# untitled.net
KiCad netlist of a schematic drawn in EAGLE
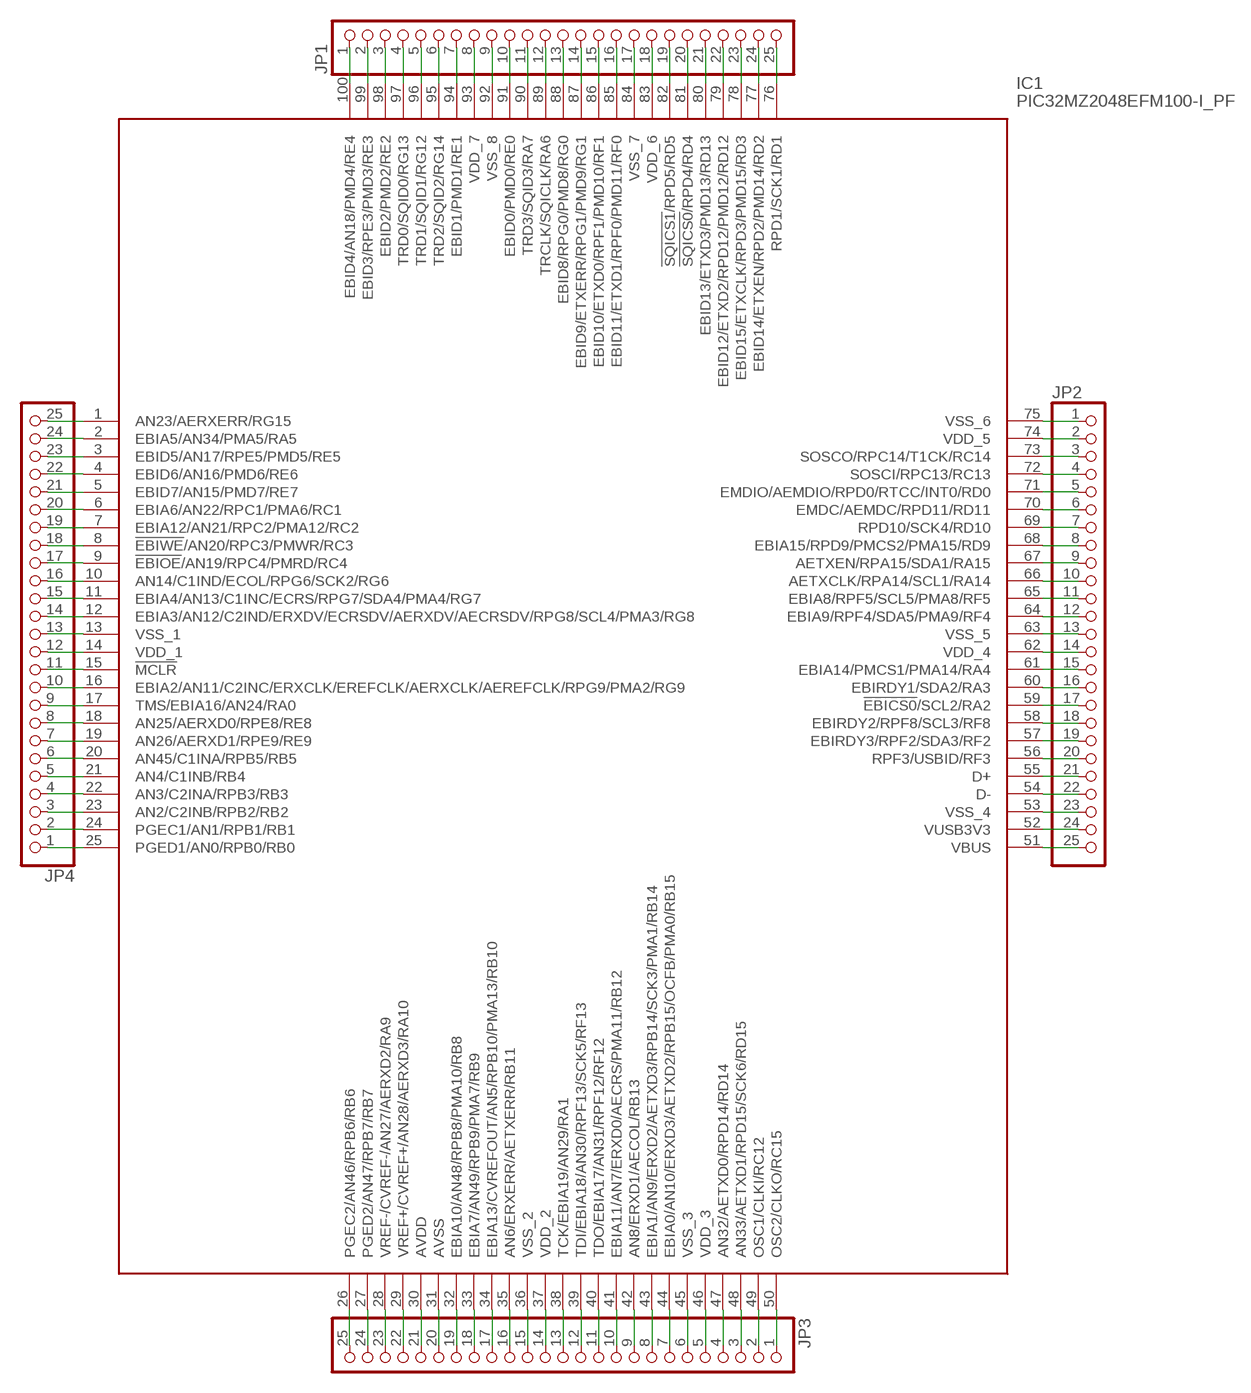
[diagram p0: schematic, sheet 1]

(export (version "E")
  (design (tool "Eeschema 10.0.6"))
  (components
    (comp (ref "IC1")
      (value "PIC32MZ2048EFM100-I_PF")
      (footprint "eagle-import:QFP50P1600X1600X120-100N")
      (fields
        (field (name "MANUFACTURER_PART_NUMBER") "PIC32MZ2048EFM100-I/PF")
        (field (name "MOUSER_PART_NUMBER") "579-MZ2048EFM100IPF")
        (field (name "RS_PART_NUMBER") "1654261")
      )
      (libsource (lib "eagle-import") (part "PIC32MZ2048EFM100-I_PF"))
    )
    (comp (ref "JP1")
      (value "PINHD-1X25")
      (footprint "eagle-import:1X25")
      (libsource (lib "eagle-import") (part "PINHD-1X25"))
    )
    (comp (ref "JP2")
      (value "PINHD-1X25")
      (footprint "eagle-import:1X25")
      (libsource (lib "eagle-import") (part "PINHD-1X25"))
    )
    (comp (ref "JP3")
      (value "PINHD-1X25")
      (footprint "eagle-import:1X25")
      (libsource (lib "eagle-import") (part "PINHD-1X25"))
    )
    (comp (ref "JP4")
      (value "PINHD-1X25")
      (footprint "eagle-import:1X25")
      (libsource (lib "eagle-import") (part "PINHD-1X25"))
    )
  )
  (nets
    (net (code "1") (name "Net-(IC1-AETXCLK{slash}RPA14{slash}SCL1{slash}RA14)") (class "Default")
      (node (ref "IC1") (pin "66") (pinfunction "AETXCLK/RPA14/SCL1/RA14_66") (pintype "bidirectional"))
      (node (ref "JP2") (pin "10") (pinfunction "10_10") (pintype "passive"))
    )
    (net (code "2") (name "Net-(IC1-AETXEN{slash}RPA15{slash}SDA1{slash}RA15)") (class "Default")
      (node (ref "IC1") (pin "67") (pinfunction "AETXEN/RPA15/SDA1/RA15_67") (pintype "bidirectional"))
      (node (ref "JP2") (pin "9") (pinfunction "9_9") (pintype "passive"))
    )
    (net (code "3") (name "Net-(IC1-AN2{slash}C2INB{slash}RPB2{slash}RB2)") (class "Default")
      (node (ref "IC1") (pin "23") (pinfunction "AN2/C2INB/RPB2/RB2_23") (pintype "bidirectional"))
      (node (ref "JP4") (pin "3") (pinfunction "3_3") (pintype "passive"))
    )
    (net (code "4") (name "Net-(IC1-AN3{slash}C2INA{slash}RPB3{slash}RB3)") (class "Default")
      (node (ref "IC1") (pin "22") (pinfunction "AN3/C2INA/RPB3/RB3_22") (pintype "bidirectional"))
      (node (ref "JP4") (pin "4") (pinfunction "4_4") (pintype "passive"))
    )
    (net (code "5") (name "Net-(IC1-AN4{slash}C1INB{slash}RB4)") (class "Default")
      (node (ref "IC1") (pin "21") (pinfunction "AN4/C1INB/RB4_21") (pintype "bidirectional"))
      (node (ref "JP4") (pin "5") (pinfunction "5_5") (pintype "passive"))
    )
    (net (code "6") (name "Net-(IC1-AN6{slash}ERXERR{slash}AETXERR{slash}RB11)") (class "Default")
      (node (ref "IC1") (pin "35") (pinfunction "AN6/ERXERR/AETXERR/RB11_35") (pintype "bidirectional"))
      (node (ref "JP3") (pin "16") (pinfunction "16_16") (pintype "passive"))
    )
    (net (code "7") (name "Net-(IC1-AN8{slash}ERXD1{slash}AECOL{slash}RB13)") (class "Default")
      (node (ref "IC1") (pin "42") (pinfunction "AN8/ERXD1/AECOL/RB13_42") (pintype "bidirectional"))
      (node (ref "JP3") (pin "9") (pinfunction "9_9") (pintype "passive"))
    )
    (net (code "8") (name "Net-(IC1-AN14{slash}C1IND{slash}ECOL{slash}RPG6{slash}SCK2{slash}RG6)") (class "Default")
      (node (ref "IC1") (pin "10") (pinfunction "AN14/C1IND/ECOL/RPG6/SCK2/RG6_10") (pintype "bidirectional"))
      (node (ref "JP4") (pin "16") (pinfunction "16_16") (pintype "passive"))
    )
    (net (code "9") (name "Net-(IC1-AN23{slash}AERXERR{slash}RG15)") (class "Default")
      (node (ref "IC1") (pin "1") (pinfunction "AN23/AERXERR/RG15_1") (pintype "bidirectional"))
      (node (ref "JP4") (pin "25") (pinfunction "25_25") (pintype "passive"))
    )
    (net (code "10") (name "Net-(IC1-AN25{slash}AERXD0{slash}RPE8{slash}RE8)") (class "Default")
      (node (ref "IC1") (pin "18") (pinfunction "AN25/AERXD0/RPE8/RE8_18") (pintype "bidirectional"))
      (node (ref "JP4") (pin "8") (pinfunction "8_8") (pintype "passive"))
    )
    (net (code "11") (name "Net-(IC1-AN26{slash}AERXD1{slash}RPE9{slash}RE9)") (class "Default")
      (node (ref "IC1") (pin "19") (pinfunction "AN26/AERXD1/RPE9/RE9_19") (pintype "bidirectional"))
      (node (ref "JP4") (pin "7") (pinfunction "7_7") (pintype "passive"))
    )
    (net (code "12") (name "Net-(IC1-AN32{slash}AETXD0{slash}RPD14{slash}RD14)") (class "Default")
      (node (ref "IC1") (pin "47") (pinfunction "AN32/AETXD0/RPD14/RD14_47") (pintype "bidirectional"))
      (node (ref "JP3") (pin "4") (pinfunction "4_4") (pintype "passive"))
    )
    (net (code "13") (name "Net-(IC1-AN33{slash}AETXD1{slash}RPD15{slash}SCK6{slash}RD15)") (class "Default")
      (node (ref "IC1") (pin "48") (pinfunction "AN33/AETXD1/RPD15/SCK6/RD15_48") (pintype "bidirectional"))
      (node (ref "JP3") (pin "3") (pinfunction "3_3") (pintype "passive"))
    )
    (net (code "14") (name "Net-(IC1-AN45{slash}C1INA{slash}RPB5{slash}RB5)") (class "Default")
      (node (ref "IC1") (pin "20") (pinfunction "AN45/C1INA/RPB5/RB5_20") (pintype "bidirectional"))
      (node (ref "JP4") (pin "6") (pinfunction "6_6") (pintype "passive"))
    )
    (net (code "15") (name "Net-(IC1-AVDD)") (class "Default")
      (node (ref "IC1") (pin "30") (pinfunction "AVDD_30") (pintype "power_in"))
      (node (ref "JP3") (pin "21") (pinfunction "21_21") (pintype "passive"))
    )
    (net (code "16") (name "Net-(IC1-AVSS)") (class "Default")
      (node (ref "IC1") (pin "31") (pinfunction "AVSS_31") (pintype "power_in"))
      (node (ref "JP3") (pin "20") (pinfunction "20_20") (pintype "passive"))
    )
    (net (code "17") (name "Net-(IC1-D+)") (class "Default")
      (node (ref "IC1") (pin "55") (pinfunction "D+_55") (pintype "bidirectional"))
      (node (ref "JP2") (pin "21") (pinfunction "21_21") (pintype "passive"))
    )
    (net (code "18") (name "Net-(IC1-D-)") (class "Default")
      (node (ref "IC1") (pin "54") (pinfunction "D-_54") (pintype "bidirectional"))
      (node (ref "JP2") (pin "22") (pinfunction "22_22") (pintype "passive"))
    )
    (net (code "19") (name "Net-(IC1-EBIA0{slash}AN10{slash}ERXD3{slash}AETXD2{slash}RPB15{slash}OCFB{slash}PMA0{slash}RB15)") (class "Default")
      (node (ref "IC1") (pin "44") (pinfunction "EBIA0/AN10/ERXD3/AETXD2/RPB15/OCFB/PMA0/RB15_44") (pintype "bidirectional"))
      (node (ref "JP3") (pin "7") (pinfunction "7_7") (pintype "passive"))
    )
    (net (code "20") (name "Net-(IC1-EBIA1{slash}AN9{slash}ERXD2{slash}AETXD3{slash}RPB14{slash}SCK3{slash}PMA1{slash}RB14)") (class "Default")
      (node (ref "IC1") (pin "43") (pinfunction "EBIA1/AN9/ERXD2/AETXD3/RPB14/SCK3/PMA1/RB14_43") (pintype "bidirectional"))
      (node (ref "JP3") (pin "8") (pinfunction "8_8") (pintype "passive"))
    )
    (net (code "21") (name "Net-(IC1-EBIA2{slash}AN11{slash}C2INC{slash}ERXCLK{slash}EREFCLK{slash}AERXCLK{slash}AEREFCLK{slash}RPG9{slash}PMA2{slash}RG9)") (class "Default")
      (node (ref "IC1") (pin "16") (pinfunction "EBIA2/AN11/C2INC/ERXCLK/EREFCLK/AERXCLK/AEREFCLK/RPG9/PMA2/RG9_16") (pintype "bidirectional"))
      (node (ref "JP4") (pin "10") (pinfunction "10_10") (pintype "passive"))
    )
    (net (code "22") (name "Net-(IC1-EBIA3{slash}AN12{slash}C2IND{slash}ERXDV{slash}ECRSDV{slash}AERXDV{slash}AECRSDV{slash}RPG8{slash}SCL4{slash}PMA3{slash}RG8)") (class "Default")
      (node (ref "IC1") (pin "12") (pinfunction "EBIA3/AN12/C2IND/ERXDV/ECRSDV/AERXDV/AECRSDV/RPG8/SCL4/PMA3/RG8_12") (pintype "bidirectional"))
      (node (ref "JP4") (pin "14") (pinfunction "14_14") (pintype "passive"))
    )
    (net (code "23") (name "Net-(IC1-EBIA4{slash}AN13{slash}C1INC{slash}ECRS{slash}RPG7{slash}SDA4{slash}PMA4{slash}RG7)") (class "Default")
      (node (ref "IC1") (pin "11") (pinfunction "EBIA4/AN13/C1INC/ECRS/RPG7/SDA4/PMA4/RG7_11") (pintype "bidirectional"))
      (node (ref "JP4") (pin "15") (pinfunction "15_15") (pintype "passive"))
    )
    (net (code "24") (name "Net-(IC1-EBIA5{slash}AN34{slash}PMA5{slash}RA5)") (class "Default")
      (node (ref "IC1") (pin "2") (pinfunction "EBIA5/AN34/PMA5/RA5_2") (pintype "bidirectional"))
      (node (ref "JP4") (pin "24") (pinfunction "24_24") (pintype "passive"))
    )
    (net (code "25") (name "Net-(IC1-EBIA6{slash}AN22{slash}RPC1{slash}PMA6{slash}RC1)") (class "Default")
      (node (ref "IC1") (pin "6") (pinfunction "EBIA6/AN22/RPC1/PMA6/RC1_6") (pintype "bidirectional"))
      (node (ref "JP4") (pin "20") (pinfunction "20_20") (pintype "passive"))
    )
    (net (code "26") (name "Net-(IC1-EBIA7{slash}AN49{slash}RPB9{slash}PMA7{slash}RB9)") (class "Default")
      (node (ref "IC1") (pin "33") (pinfunction "EBIA7/AN49/RPB9/PMA7/RB9_33") (pintype "bidirectional"))
      (node (ref "JP3") (pin "18") (pinfunction "18_18") (pintype "passive"))
    )
    (net (code "27") (name "Net-(IC1-EBIA8{slash}RPF5{slash}SCL5{slash}PMA8{slash}RF5)") (class "Default")
      (node (ref "IC1") (pin "65") (pinfunction "EBIA8/RPF5/SCL5/PMA8/RF5_65") (pintype "bidirectional"))
      (node (ref "JP2") (pin "11") (pinfunction "11_11") (pintype "passive"))
    )
    (net (code "28") (name "Net-(IC1-EBIA9{slash}RPF4{slash}SDA5{slash}PMA9{slash}RF4)") (class "Default")
      (node (ref "IC1") (pin "64") (pinfunction "EBIA9/RPF4/SDA5/PMA9/RF4_64") (pintype "bidirectional"))
      (node (ref "JP2") (pin "12") (pinfunction "12_12") (pintype "passive"))
    )
    (net (code "29") (name "Net-(IC1-EBIA10{slash}AN48{slash}RPB8{slash}PMA10{slash}RB8)") (class "Default")
      (node (ref "IC1") (pin "32") (pinfunction "EBIA10/AN48/RPB8/PMA10/RB8_32") (pintype "bidirectional"))
      (node (ref "JP3") (pin "19") (pinfunction "19_19") (pintype "passive"))
    )
    (net (code "30") (name "Net-(IC1-EBIA11{slash}AN7{slash}ERXD0{slash}AECRS{slash}PMA11{slash}RB12)") (class "Default")
      (node (ref "IC1") (pin "41") (pinfunction "EBIA11/AN7/ERXD0/AECRS/PMA11/RB12_41") (pintype "bidirectional"))
      (node (ref "JP3") (pin "10") (pinfunction "10_10") (pintype "passive"))
    )
    (net (code "31") (name "Net-(IC1-EBIA12{slash}AN21{slash}RPC2{slash}PMA12{slash}RC2)") (class "Default")
      (node (ref "IC1") (pin "7") (pinfunction "EBIA12/AN21/RPC2/PMA12/RC2_7") (pintype "bidirectional"))
      (node (ref "JP4") (pin "19") (pinfunction "19_19") (pintype "passive"))
    )
    (net (code "32") (name "Net-(IC1-EBIA13{slash}CVREFOUT{slash}AN5{slash}RPB10{slash}PMA13{slash}RB10)") (class "Default")
      (node (ref "IC1") (pin "34") (pinfunction "EBIA13/CVREFOUT/AN5/RPB10/PMA13/RB10_34") (pintype "bidirectional"))
      (node (ref "JP3") (pin "17") (pinfunction "17_17") (pintype "passive"))
    )
    (net (code "33") (name "Net-(IC1-EBIA14{slash}PMCS1{slash}PMA14{slash}RA4)") (class "Default")
      (node (ref "IC1") (pin "61") (pinfunction "EBIA14/PMCS1/PMA14/RA4_61") (pintype "bidirectional"))
      (node (ref "JP2") (pin "15") (pinfunction "15_15") (pintype "passive"))
    )
    (net (code "34") (name "Net-(IC1-EBIA15{slash}RPD9{slash}PMCS2{slash}PMA15{slash}RD9)") (class "Default")
      (node (ref "IC1") (pin "68") (pinfunction "EBIA15/RPD9/PMCS2/PMA15/RD9_68") (pintype "bidirectional"))
      (node (ref "JP2") (pin "8") (pinfunction "8_8") (pintype "passive"))
    )
    (net (code "35") (name "Net-(IC1-EBID0{slash}PMD0{slash}RE0)") (class "Default")
      (node (ref "IC1") (pin "91") (pinfunction "EBID0/PMD0/RE0_91") (pintype "bidirectional"))
      (node (ref "JP1") (pin "10") (pinfunction "10_10") (pintype "passive"))
    )
    (net (code "36") (name "Net-(IC1-EBID1{slash}PMD1{slash}RE1)") (class "Default")
      (node (ref "IC1") (pin "94") (pinfunction "EBID1/PMD1/RE1_94") (pintype "bidirectional"))
      (node (ref "JP1") (pin "7") (pinfunction "7_7") (pintype "passive"))
    )
    (net (code "37") (name "Net-(IC1-EBID2{slash}PMD2{slash}RE2)") (class "Default")
      (node (ref "IC1") (pin "98") (pinfunction "EBID2/PMD2/RE2_98") (pintype "bidirectional"))
      (node (ref "JP1") (pin "3") (pinfunction "3_3") (pintype "passive"))
    )
    (net (code "38") (name "Net-(IC1-EBID3{slash}RPE3{slash}PMD3{slash}RE3)") (class "Default")
      (node (ref "IC1") (pin "99") (pinfunction "EBID3/RPE3/PMD3/RE3_99") (pintype "bidirectional"))
      (node (ref "JP1") (pin "2") (pinfunction "2_2") (pintype "passive"))
    )
    (net (code "39") (name "Net-(IC1-EBID4{slash}AN18{slash}PMD4{slash}RE4)") (class "Default")
      (node (ref "IC1") (pin "100") (pinfunction "EBID4/AN18/PMD4/RE4_100") (pintype "bidirectional"))
      (node (ref "JP1") (pin "1") (pinfunction "1_1") (pintype "passive"))
    )
    (net (code "40") (name "Net-(IC1-EBID5{slash}AN17{slash}RPE5{slash}PMD5{slash}RE5)") (class "Default")
      (node (ref "IC1") (pin "3") (pinfunction "EBID5/AN17/RPE5/PMD5/RE5_3") (pintype "bidirectional"))
      (node (ref "JP4") (pin "23") (pinfunction "23_23") (pintype "passive"))
    )
    (net (code "41") (name "Net-(IC1-EBID6{slash}AN16{slash}PMD6{slash}RE6)") (class "Default")
      (node (ref "IC1") (pin "4") (pinfunction "EBID6/AN16/PMD6/RE6_4") (pintype "bidirectional"))
      (node (ref "JP4") (pin "22") (pinfunction "22_22") (pintype "passive"))
    )
    (net (code "42") (name "Net-(IC1-EBID7{slash}AN15{slash}PMD7{slash}RE7)") (class "Default")
      (node (ref "IC1") (pin "5") (pinfunction "EBID7/AN15/PMD7/RE7_5") (pintype "bidirectional"))
      (node (ref "JP4") (pin "21") (pinfunction "21_21") (pintype "passive"))
    )
    (net (code "43") (name "Net-(IC1-EBID8{slash}RPG0{slash}PMD8{slash}RG0)") (class "Default")
      (node (ref "IC1") (pin "88") (pinfunction "EBID8/RPG0/PMD8/RG0_88") (pintype "bidirectional"))
      (node (ref "JP1") (pin "13") (pinfunction "13_13") (pintype "passive"))
    )
    (net (code "44") (name "Net-(IC1-EBID9{slash}ETXERR{slash}RPG1{slash}PMD9{slash}RG1)") (class "Default")
      (node (ref "IC1") (pin "87") (pinfunction "EBID9/ETXERR/RPG1/PMD9/RG1_87") (pintype "bidirectional"))
      (node (ref "JP1") (pin "14") (pinfunction "14_14") (pintype "passive"))
    )
    (net (code "45") (name "Net-(IC1-EBID10{slash}ETXD0{slash}RPF1{slash}PMD10{slash}RF1)") (class "Default")
      (node (ref "IC1") (pin "86") (pinfunction "EBID10/ETXD0/RPF1/PMD10/RF1_86") (pintype "bidirectional"))
      (node (ref "JP1") (pin "15") (pinfunction "15_15") (pintype "passive"))
    )
    (net (code "46") (name "Net-(IC1-EBID11{slash}ETXD1{slash}RPF0{slash}PMD11{slash}RF0)") (class "Default")
      (node (ref "IC1") (pin "85") (pinfunction "EBID11/ETXD1/RPF0/PMD11/RF0_85") (pintype "bidirectional"))
      (node (ref "JP1") (pin "16") (pinfunction "16_16") (pintype "passive"))
    )
    (net (code "47") (name "Net-(IC1-EBID12{slash}ETXD2{slash}RPD12{slash}PMD12{slash}RD12)") (class "Default")
      (node (ref "IC1") (pin "79") (pinfunction "EBID12/ETXD2/RPD12/PMD12/RD12_79") (pintype "bidirectional"))
      (node (ref "JP1") (pin "22") (pinfunction "22_22") (pintype "passive"))
    )
    (net (code "48") (name "Net-(IC1-EBID13{slash}ETXD3{slash}PMD13{slash}RD13)") (class "Default")
      (node (ref "IC1") (pin "80") (pinfunction "EBID13/ETXD3/PMD13/RD13_80") (pintype "bidirectional"))
      (node (ref "JP1") (pin "21") (pinfunction "21_21") (pintype "passive"))
    )
    (net (code "49") (name "Net-(IC1-EBID14{slash}ETXEN{slash}RPD2{slash}PMD14{slash}RD2)") (class "Default")
      (node (ref "IC1") (pin "77") (pinfunction "EBID14/ETXEN/RPD2/PMD14/RD2_77") (pintype "bidirectional"))
      (node (ref "JP1") (pin "24") (pinfunction "24_24") (pintype "passive"))
    )
    (net (code "50") (name "Net-(IC1-EBID15{slash}ETXCLK{slash}RPD3{slash}PMD15{slash}RD3)") (class "Default")
      (node (ref "IC1") (pin "78") (pinfunction "EBID15/ETXCLK/RPD3/PMD15/RD3_78") (pintype "bidirectional"))
      (node (ref "JP1") (pin "23") (pinfunction "23_23") (pintype "passive"))
    )
    (net (code "51") (name "Net-(IC1-EBIRDY1{slash}SDA2{slash}RA3)") (class "Default")
      (node (ref "IC1") (pin "60") (pinfunction "EBIRDY1/SDA2/RA3_60") (pintype "bidirectional"))
      (node (ref "JP2") (pin "16") (pinfunction "16_16") (pintype "passive"))
    )
    (net (code "52") (name "Net-(IC1-EBIRDY2{slash}RPF8{slash}SCL3{slash}RF8)") (class "Default")
      (node (ref "IC1") (pin "58") (pinfunction "EBIRDY2/RPF8/SCL3/RF8_58") (pintype "bidirectional"))
      (node (ref "JP2") (pin "18") (pinfunction "18_18") (pintype "passive"))
    )
    (net (code "53") (name "Net-(IC1-EBIRDY3{slash}RPF2{slash}SDA3{slash}RF2)") (class "Default")
      (node (ref "IC1") (pin "57") (pinfunction "EBIRDY3/RPF2/SDA3/RF2_57") (pintype "bidirectional"))
      (node (ref "JP2") (pin "19") (pinfunction "19_19") (pintype "passive"))
    )
    (net (code "54") (name "Net-(IC1-EMDC{slash}AEMDC{slash}RPD11{slash}RD11)") (class "Default")
      (node (ref "IC1") (pin "70") (pinfunction "EMDC/AEMDC/RPD11/RD11_70") (pintype "bidirectional"))
      (node (ref "JP2") (pin "6") (pinfunction "6_6") (pintype "passive"))
    )
    (net (code "55") (name "Net-(IC1-EMDIO{slash}AEMDIO{slash}RPD0{slash}RTCC{slash}INT0{slash}RD0)") (class "Default")
      (node (ref "IC1") (pin "71") (pinfunction "EMDIO/AEMDIO/RPD0/RTCC/INT0/RD0_71") (pintype "bidirectional"))
      (node (ref "JP2") (pin "5") (pinfunction "5_5") (pintype "passive"))
    )
    (net (code "56") (name "Net-(IC1-OSC1{slash}CLKI{slash}RC12)") (class "Default")
      (node (ref "IC1") (pin "49") (pinfunction "OSC1/CLKI/RC12_49") (pintype "bidirectional"))
      (node (ref "JP3") (pin "2") (pinfunction "2_2") (pintype "passive"))
    )
    (net (code "57") (name "Net-(IC1-OSC2{slash}CLKO{slash}RC15)") (class "Default")
      (node (ref "IC1") (pin "50") (pinfunction "OSC2/CLKO/RC15_50") (pintype "bidirectional"))
      (node (ref "JP3") (pin "1") (pinfunction "1_1") (pintype "passive"))
    )
    (net (code "58") (name "Net-(IC1-PGEC1{slash}AN1{slash}RPB1{slash}RB1)") (class "Default")
      (node (ref "IC1") (pin "24") (pinfunction "PGEC1/AN1/RPB1/RB1_24") (pintype "bidirectional"))
      (node (ref "JP4") (pin "2") (pinfunction "2_2") (pintype "passive"))
    )
    (net (code "59") (name "Net-(IC1-PGEC2{slash}AN46{slash}RPB6{slash}RB6)") (class "Default")
      (node (ref "IC1") (pin "26") (pinfunction "PGEC2/AN46/RPB6/RB6_26") (pintype "bidirectional"))
      (node (ref "JP3") (pin "25") (pinfunction "25_25") (pintype "passive"))
    )
    (net (code "60") (name "Net-(IC1-PGED1{slash}AN0{slash}RPB0{slash}RB0)") (class "Default")
      (node (ref "IC1") (pin "25") (pinfunction "PGED1/AN0/RPB0/RB0_25") (pintype "bidirectional"))
      (node (ref "JP4") (pin "1") (pinfunction "1_1") (pintype "passive"))
    )
    (net (code "61") (name "Net-(IC1-PGED2{slash}AN47{slash}RPB7{slash}RB7)") (class "Default")
      (node (ref "IC1") (pin "27") (pinfunction "PGED2/AN47/RPB7/RB7_27") (pintype "bidirectional"))
      (node (ref "JP3") (pin "24") (pinfunction "24_24") (pintype "passive"))
    )
    (net (code "62") (name "Net-(IC1-RPD1{slash}SCK1{slash}RD1)") (class "Default")
      (node (ref "IC1") (pin "76") (pinfunction "RPD1/SCK1/RD1_76") (pintype "bidirectional"))
      (node (ref "JP1") (pin "25") (pinfunction "25_25") (pintype "passive"))
    )
    (net (code "63") (name "Net-(IC1-RPD10{slash}SCK4{slash}RD10)") (class "Default")
      (node (ref "IC1") (pin "69") (pinfunction "RPD10/SCK4/RD10_69") (pintype "bidirectional"))
      (node (ref "JP2") (pin "7") (pinfunction "7_7") (pintype "passive"))
    )
    (net (code "64") (name "Net-(IC1-RPF3{slash}USBID{slash}RF3)") (class "Default")
      (node (ref "IC1") (pin "56") (pinfunction "RPF3/USBID/RF3_56") (pintype "bidirectional"))
      (node (ref "JP2") (pin "20") (pinfunction "20_20") (pintype "passive"))
    )
    (net (code "65") (name "Net-(IC1-SOSCI{slash}RPC13{slash}RC13)") (class "Default")
      (node (ref "IC1") (pin "72") (pinfunction "SOSCI/RPC13/RC13_72") (pintype "bidirectional"))
      (node (ref "JP2") (pin "4") (pinfunction "4_4") (pintype "passive"))
    )
    (net (code "66") (name "Net-(IC1-SOSCO{slash}RPC14{slash}T1CK{slash}RC14)") (class "Default")
      (node (ref "IC1") (pin "73") (pinfunction "SOSCO/RPC14/T1CK/RC14_73") (pintype "bidirectional"))
      (node (ref "JP2") (pin "3") (pinfunction "3_3") (pintype "passive"))
    )
    (net (code "67") (name "Net-(IC1-TCK{slash}EBIA19{slash}AN29{slash}RA1)") (class "Default")
      (node (ref "IC1") (pin "38") (pinfunction "TCK/EBIA19/AN29/RA1_38") (pintype "bidirectional"))
      (node (ref "JP3") (pin "13") (pinfunction "13_13") (pintype "passive"))
    )
    (net (code "68") (name "Net-(IC1-TDI{slash}EBIA18{slash}AN30{slash}RPF13{slash}SCK5{slash}RF13)") (class "Default")
      (node (ref "IC1") (pin "39") (pinfunction "TDI/EBIA18/AN30/RPF13/SCK5/RF13_39") (pintype "bidirectional"))
      (node (ref "JP3") (pin "12") (pinfunction "12_12") (pintype "passive"))
    )
    (net (code "69") (name "Net-(IC1-TDO{slash}EBIA17{slash}AN31{slash}RPF12{slash}RF12)") (class "Default")
      (node (ref "IC1") (pin "40") (pinfunction "TDO/EBIA17/AN31/RPF12/RF12_40") (pintype "bidirectional"))
      (node (ref "JP3") (pin "11") (pinfunction "11_11") (pintype "passive"))
    )
    (net (code "70") (name "Net-(IC1-TMS{slash}EBIA16{slash}AN24{slash}RA0)") (class "Default")
      (node (ref "IC1") (pin "17") (pinfunction "TMS/EBIA16/AN24/RA0_17") (pintype "bidirectional"))
      (node (ref "JP4") (pin "9") (pinfunction "9_9") (pintype "passive"))
    )
    (net (code "71") (name "Net-(IC1-TRCLK{slash}SQICLK{slash}RA6)") (class "Default")
      (node (ref "IC1") (pin "89") (pinfunction "TRCLK/SQICLK/RA6_89") (pintype "bidirectional"))
      (node (ref "JP1") (pin "12") (pinfunction "12_12") (pintype "passive"))
    )
    (net (code "72") (name "Net-(IC1-TRD0{slash}SQID0{slash}RG13)") (class "Default")
      (node (ref "IC1") (pin "97") (pinfunction "TRD0/SQID0/RG13_97") (pintype "bidirectional"))
      (node (ref "JP1") (pin "4") (pinfunction "4_4") (pintype "passive"))
    )
    (net (code "73") (name "Net-(IC1-TRD1{slash}SQID1{slash}RG12)") (class "Default")
      (node (ref "IC1") (pin "96") (pinfunction "TRD1/SQID1/RG12_96") (pintype "bidirectional"))
      (node (ref "JP1") (pin "5") (pinfunction "5_5") (pintype "passive"))
    )
    (net (code "74") (name "Net-(IC1-TRD2{slash}SQID2{slash}RG14)") (class "Default")
      (node (ref "IC1") (pin "95") (pinfunction "TRD2/SQID2/RG14_95") (pintype "bidirectional"))
      (node (ref "JP1") (pin "6") (pinfunction "6_6") (pintype "passive"))
    )
    (net (code "75") (name "Net-(IC1-TRD3{slash}SQID3{slash}RA7)") (class "Default")
      (node (ref "IC1") (pin "90") (pinfunction "TRD3/SQID3/RA7_90") (pintype "bidirectional"))
      (node (ref "JP1") (pin "11") (pinfunction "11_11") (pintype "passive"))
    )
    (net (code "76") (name "Net-(IC1-VBUS)") (class "Default")
      (node (ref "IC1") (pin "51") (pinfunction "VBUS_51") (pintype "power_in"))
      (node (ref "JP2") (pin "25") (pinfunction "25_25") (pintype "passive"))
    )
    (net (code "77") (name "Net-(IC1-VDD_1)") (class "Default")
      (node (ref "IC1") (pin "14") (pinfunction "VDD_1_14") (pintype "power_in"))
      (node (ref "JP4") (pin "12") (pinfunction "12_12") (pintype "passive"))
    )
    (net (code "78") (name "Net-(IC1-VDD_2)") (class "Default")
      (node (ref "IC1") (pin "37") (pinfunction "VDD_2_37") (pintype "power_in"))
      (node (ref "JP3") (pin "14") (pinfunction "14_14") (pintype "passive"))
    )
    (net (code "79") (name "Net-(IC1-VDD_3)") (class "Default")
      (node (ref "IC1") (pin "46") (pinfunction "VDD_3_46") (pintype "power_in"))
      (node (ref "JP3") (pin "5") (pinfunction "5_5") (pintype "passive"))
    )
    (net (code "80") (name "Net-(IC1-VDD_4)") (class "Default")
      (node (ref "IC1") (pin "62") (pinfunction "VDD_4_62") (pintype "power_in"))
      (node (ref "JP2") (pin "14") (pinfunction "14_14") (pintype "passive"))
    )
    (net (code "81") (name "Net-(IC1-VDD_5)") (class "Default")
      (node (ref "IC1") (pin "74") (pinfunction "VDD_5_74") (pintype "power_in"))
      (node (ref "JP2") (pin "2") (pinfunction "2_2") (pintype "passive"))
    )
    (net (code "82") (name "Net-(IC1-VDD_6)") (class "Default")
      (node (ref "IC1") (pin "83") (pinfunction "VDD_6_83") (pintype "power_in"))
      (node (ref "JP1") (pin "18") (pinfunction "18_18") (pintype "passive"))
    )
    (net (code "83") (name "Net-(IC1-VDD_7)") (class "Default")
      (node (ref "IC1") (pin "93") (pinfunction "VDD_7_93") (pintype "power_in"))
      (node (ref "JP1") (pin "8") (pinfunction "8_8") (pintype "passive"))
    )
    (net (code "84") (name "Net-(IC1-VREF+{slash}CVREF+{slash}AN28{slash}AERXD3{slash}RA10)") (class "Default")
      (node (ref "IC1") (pin "29") (pinfunction "VREF+/CVREF+/AN28/AERXD3/RA10_29") (pintype "bidirectional"))
      (node (ref "JP3") (pin "22") (pinfunction "22_22") (pintype "passive"))
    )
    (net (code "85") (name "Net-(IC1-VREF-{slash}CVREF-{slash}AN27{slash}AERXD2{slash}RA9)") (class "Default")
      (node (ref "IC1") (pin "28") (pinfunction "VREF-/CVREF-/AN27/AERXD2/RA9_28") (pintype "bidirectional"))
      (node (ref "JP3") (pin "23") (pinfunction "23_23") (pintype "passive"))
    )
    (net (code "86") (name "Net-(IC1-VSS_1)") (class "Default")
      (node (ref "IC1") (pin "13") (pinfunction "VSS_1_13") (pintype "power_in"))
      (node (ref "JP4") (pin "13") (pinfunction "13_13") (pintype "passive"))
    )
    (net (code "87") (name "Net-(IC1-VSS_2)") (class "Default")
      (node (ref "IC1") (pin "36") (pinfunction "VSS_2_36") (pintype "power_in"))
      (node (ref "JP3") (pin "15") (pinfunction "15_15") (pintype "passive"))
    )
    (net (code "88") (name "Net-(IC1-VSS_3)") (class "Default")
      (node (ref "IC1") (pin "45") (pinfunction "VSS_3_45") (pintype "power_in"))
      (node (ref "JP3") (pin "6") (pinfunction "6_6") (pintype "passive"))
    )
    (net (code "89") (name "Net-(IC1-VSS_4)") (class "Default")
      (node (ref "IC1") (pin "53") (pinfunction "VSS_4_53") (pintype "power_in"))
      (node (ref "JP2") (pin "23") (pinfunction "23_23") (pintype "passive"))
    )
    (net (code "90") (name "Net-(IC1-VSS_5)") (class "Default")
      (node (ref "IC1") (pin "63") (pinfunction "VSS_5_63") (pintype "power_in"))
      (node (ref "JP2") (pin "13") (pinfunction "13_13") (pintype "passive"))
    )
    (net (code "91") (name "Net-(IC1-VSS_6)") (class "Default")
      (node (ref "IC1") (pin "75") (pinfunction "VSS_6_75") (pintype "power_in"))
      (node (ref "JP2") (pin "1") (pinfunction "1_1") (pintype "passive"))
    )
    (net (code "92") (name "Net-(IC1-VSS_7)") (class "Default")
      (node (ref "IC1") (pin "84") (pinfunction "VSS_7_84") (pintype "power_in"))
      (node (ref "JP1") (pin "17") (pinfunction "17_17") (pintype "passive"))
    )
    (net (code "93") (name "Net-(IC1-VSS_8)") (class "Default")
      (node (ref "IC1") (pin "92") (pinfunction "VSS_8_92") (pintype "power_in"))
      (node (ref "JP1") (pin "9") (pinfunction "9_9") (pintype "passive"))
    )
    (net (code "94") (name "Net-(IC1-VUSB3V3)") (class "Default")
      (node (ref "IC1") (pin "52") (pinfunction "VUSB3V3_52") (pintype "power_in"))
      (node (ref "JP2") (pin "24") (pinfunction "24_24") (pintype "passive"))
    )
    (net (code "95") (name "Net-(IC1-~{EBICS0}{slash}SCL2{slash}RA2)") (class "Default")
      (node (ref "IC1") (pin "59") (pinfunction "~{EBICS0}/SCL2/RA2_59") (pintype "bidirectional"))
      (node (ref "JP2") (pin "17") (pinfunction "17_17") (pintype "passive"))
    )
    (net (code "96") (name "Net-(IC1-~{EBIOE}{slash}AN19{slash}RPC4{slash}PMRD{slash}RC4)") (class "Default")
      (node (ref "IC1") (pin "9") (pinfunction "~{EBIOE}/AN19/RPC4/PMRD/RC4_9") (pintype "bidirectional"))
      (node (ref "JP4") (pin "17") (pinfunction "17_17") (pintype "passive"))
    )
    (net (code "97") (name "Net-(IC1-~{EBIWE}{slash}AN20{slash}RPC3{slash}PMWR{slash}RC3)") (class "Default")
      (node (ref "IC1") (pin "8") (pinfunction "~{EBIWE}/AN20/RPC3/PMWR/RC3_8") (pintype "bidirectional"))
      (node (ref "JP4") (pin "18") (pinfunction "18_18") (pintype "passive"))
    )
    (net (code "98") (name "Net-(IC1-~{MCLR})") (class "Default")
      (node (ref "IC1") (pin "15") (pinfunction "~{MCLR}_15") (pintype "input"))
      (node (ref "JP4") (pin "11") (pinfunction "11_11") (pintype "passive"))
    )
    (net (code "99") (name "Net-(IC1-~{SQICS0}{slash}RPD4{slash}RD4)") (class "Default")
      (node (ref "IC1") (pin "81") (pinfunction "~{SQICS0}/RPD4/RD4_81") (pintype "bidirectional"))
      (node (ref "JP1") (pin "20") (pinfunction "20_20") (pintype "passive"))
    )
    (net (code "100") (name "Net-(IC1-~{SQICS1}{slash}RPD5{slash}RD5)") (class "Default")
      (node (ref "IC1") (pin "82") (pinfunction "~{SQICS1}/RPD5/RD5_82") (pintype "bidirectional"))
      (node (ref "JP1") (pin "19") (pinfunction "19_19") (pintype "passive"))
    )
  )
)
